# SWD-IR-V01-003.net
KiCad netlist of a schematic drawn in EAGLE
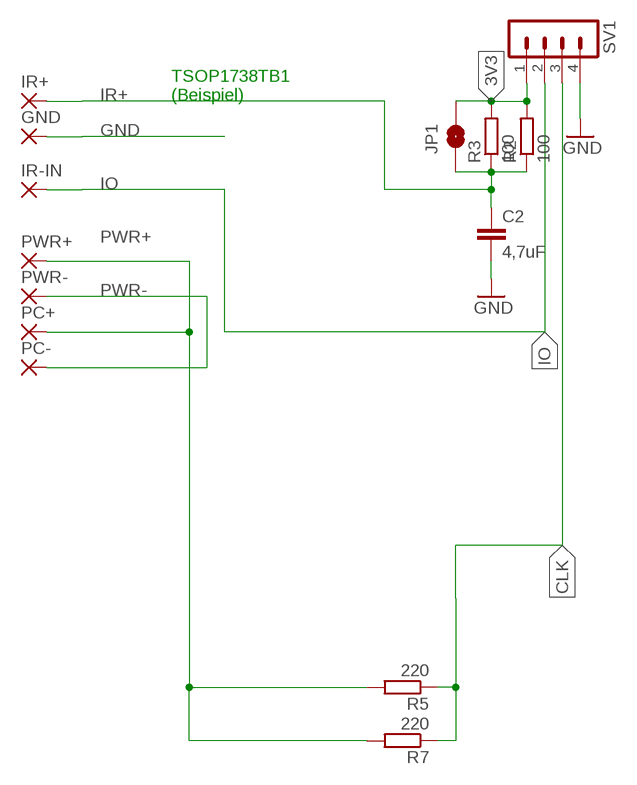
[diagram p0: schematic, sheet 1]

(export (version "E")
  (design (tool "Eeschema 10.0.6"))
  (components
    (comp (ref "C2")
      (value "4,7uF")
      (footprint "eagle-import:C1206K")
      (libsource (lib "eagle-import") (part "C-EUC1206K"))
    )
    (comp (ref "GND")
      (value "SMD2")
      (footprint "eagle-import:SMD1,27-2,54")
      (libsource (lib "eagle-import") (part "SMD2"))
    )
    (comp (ref "IR+")
      (value "SMD2")
      (footprint "eagle-import:SMD1,27-2,54")
      (libsource (lib "eagle-import") (part "SMD2"))
    )
    (comp (ref "IR-IN")
      (value "SMD2")
      (footprint "eagle-import:SMD1,27-2,54")
      (libsource (lib "eagle-import") (part "SMD2"))
    )
    (comp (ref "JP1")
      (value "JUMPER-SMT_2_NO_NO-SILK")
      (footprint "eagle-import:SMT-JUMPER_2_NO_NO-SILK")
      (libsource (lib "eagle-import") (part "JUMPER-SMT_2_NO_NO-SILK"))
    )
    (comp (ref "PC+")
      (value "SMD2")
      (footprint "eagle-import:SMD1,27-2,54")
      (libsource (lib "eagle-import") (part "SMD2"))
    )
    (comp (ref "PC-")
      (value "SMD2")
      (footprint "eagle-import:SMD1,27-2,54")
      (libsource (lib "eagle-import") (part "SMD2"))
    )
    (comp (ref "PWR+")
      (value "SMD2")
      (footprint "eagle-import:SMD1,27-2,54")
      (libsource (lib "eagle-import") (part "SMD2"))
    )
    (comp (ref "PWR-")
      (value "SMD2")
      (footprint "eagle-import:SMD1,27-2,54")
      (libsource (lib "eagle-import") (part "SMD2"))
    )
    (comp (ref "R2")
      (value "100")
      (footprint "eagle-import:0204_7")
      (libsource (lib "eagle-import") (part "R-EU_0204/7"))
    )
    (comp (ref "R3")
      (value "100")
      (footprint "eagle-import:R0805W")
      (libsource (lib "eagle-import") (part "R-EU_R0805W"))
    )
    (comp (ref "R5")
      (value "220")
      (footprint "eagle-import:0204_7")
      (libsource (lib "eagle-import") (part "R-EU_0204/7"))
    )
    (comp (ref "R7")
      (value "220")
      (footprint "eagle-import:R0805W")
      (libsource (lib "eagle-import") (part "R-EU_R0805W"))
    )
    (comp (ref "SV1")
      (value "MA04-1")
      (footprint "eagle-import:MA04-1")
      (libsource (lib "eagle-import") (part "MA04-1"))
    )
  )
  (nets
    (net (code "1") (name "/IR+") (class "Default")
      (node (ref "C2") (pin "1") (pinfunction "1_1") (pintype "passive"))
      (node (ref "IR+") (pin "1") (pinfunction "P_1") (pintype "passive"))
      (node (ref "JP1") (pin "1") (pinfunction "1_1") (pintype "passive"))
      (node (ref "R2") (pin "1") (pinfunction "1_1") (pintype "passive"))
      (node (ref "R3") (pin "1") (pinfunction "1_1") (pintype "passive"))
    )
    (net (code "2") (name "/PWR+") (class "Default")
      (node (ref "PC+") (pin "1") (pinfunction "P_1") (pintype "passive"))
      (node (ref "PWR+") (pin "1") (pinfunction "P_1") (pintype "passive"))
      (node (ref "R5") (pin "2") (pinfunction "2_2") (pintype "passive"))
      (node (ref "R7") (pin "2") (pinfunction "2_2") (pintype "passive"))
    )
    (net (code "3") (name "/PWR-") (class "Default")
      (node (ref "PC-") (pin "1") (pinfunction "P_1") (pintype "passive"))
      (node (ref "PWR-") (pin "1") (pinfunction "P_1") (pintype "passive"))
    )
    (net (code "4") (name "3V3") (class "Default")
      (node (ref "JP1") (pin "2") (pinfunction "2_2") (pintype "passive"))
      (node (ref "R2") (pin "2") (pinfunction "2_2") (pintype "passive"))
      (node (ref "R3") (pin "2") (pinfunction "2_2") (pintype "passive"))
      (node (ref "SV1") (pin "1") (pinfunction "1_1") (pintype "passive"))
    )
    (net (code "5") (name "CLK") (class "Default")
      (node (ref "R5") (pin "1") (pinfunction "1_1") (pintype "passive"))
      (node (ref "R7") (pin "1") (pinfunction "1_1") (pintype "passive"))
      (node (ref "SV1") (pin "3") (pinfunction "3_3") (pintype "passive"))
    )
    (net (code "6") (name "GND") (class "Default")
      (node (ref "C2") (pin "2") (pinfunction "2_2") (pintype "passive"))
      (node (ref "GND") (pin "1") (pinfunction "P_1") (pintype "passive"))
      (node (ref "SV1") (pin "4") (pinfunction "4_4") (pintype "passive"))
    )
    (net (code "7") (name "IO") (class "Default")
      (node (ref "IR-IN") (pin "1") (pinfunction "P_1") (pintype "passive"))
      (node (ref "SV1") (pin "2") (pinfunction "2_2") (pintype "passive"))
    )
  )
)
